# adc12-st.net
KiCad netlist of a schematic drawn in EAGLE
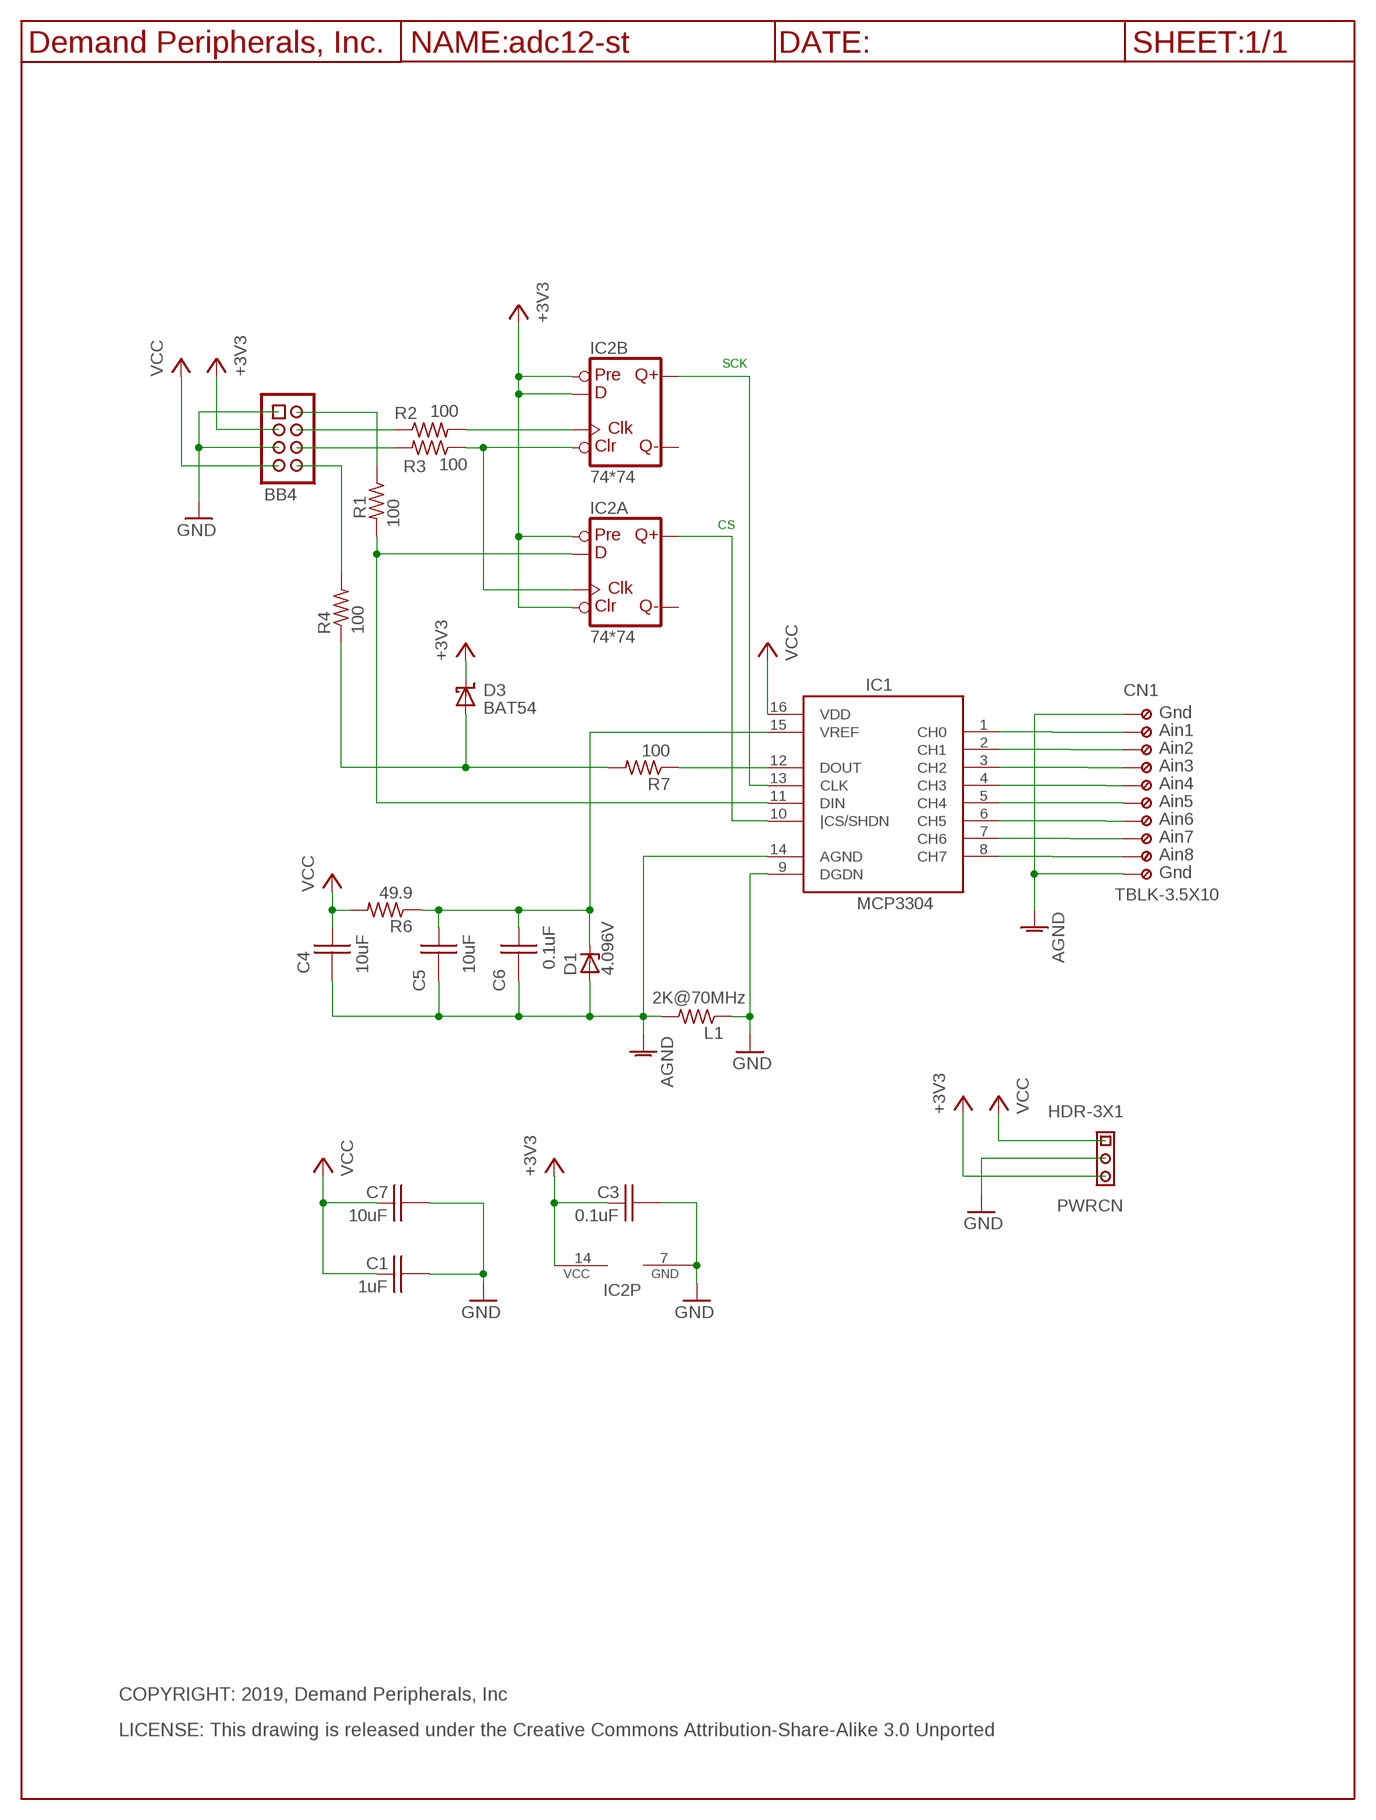
[diagram p0: schematic, sheet 1]

(export (version "E")
  (design (tool "Eeschema 10.0.6"))
  (components
    (comp (ref "BB4")
      (value "BB4_CON")
      (footprint "eagle-import:HDR-4X2")
      (libsource (lib "eagle-import") (part "HDR-4X2-SHR"))
    )
    (comp (ref "C1")
      (value "1uF")
      (footprint "eagle-import:C0603")
      (libsource (lib "eagle-import") (part "C1.0UF_C0603"))
    )
    (comp (ref "C3")
      (value "0.1uF")
      (footprint "eagle-import:C0603")
      (libsource (lib "eagle-import") (part "C0.1UF_C0603"))
    )
    (comp (ref "C4")
      (value "10uF")
      (footprint "eagle-import:C0805")
      (libsource (lib "eagle-import") (part "C10UF35V_C0805"))
    )
    (comp (ref "C5")
      (value "10uF")
      (footprint "eagle-import:C0805")
      (libsource (lib "eagle-import") (part "C10UF35V_C0805"))
    )
    (comp (ref "C6")
      (value "0.1uF")
      (footprint "eagle-import:C0603")
      (libsource (lib "eagle-import") (part "C0.1UF_C0603"))
    )
    (comp (ref "C7")
      (value "10uF")
      (footprint "eagle-import:C0805")
      (libsource (lib "eagle-import") (part "C10UF35V_C0805"))
    )
    (comp (ref "CN1")
      (value "TBLK-3.5X10")
      (footprint "eagle-import:TBLK-3.5X10")
      (libsource (lib "eagle-import") (part "TBLK-3.5X10"))
    )
    (comp (ref "D1")
      (value "4.096V")
      (footprint "eagle-import:SOT23")
      (libsource (lib "eagle-import") (part "LM4040"))
    )
    (comp (ref "D3")
      (value "BAT54")
      (footprint "eagle-import:SOT23")
      (libsource (lib "eagle-import") (part "BAT54"))
    )
    (comp (ref "IC1")
      (value "MCP3304")
      (footprint "eagle-import:SO16")
      (libsource (lib "eagle-import") (part "MCP3304"))
    )
    (comp (ref "IC2")
      (value "74*74")
      (footprint "eagle-import:SO14")
      (libsource (lib "eagle-import") (part "74AHC74SS"))
    )
    (comp (ref "L1")
      (value "2K@70MHz")
      (footprint "eagle-import:R0805")
      (libsource (lib "eagle-import") (part "L2K70MHZR0805"))
    )
    (comp (ref "PWRCN")
      (value "HDR-3X1")
      (footprint "eagle-import:HDR-3X1")
      (libsource (lib "eagle-import") (part "HDR-3X1"))
    )
    (comp (ref "R1")
      (value "100")
      (footprint "eagle-import:R0603")
      (libsource (lib "eagle-import") (part "R100_R0603"))
    )
    (comp (ref "R2")
      (value "100")
      (footprint "eagle-import:R0603")
      (libsource (lib "eagle-import") (part "R100_R0603"))
    )
    (comp (ref "R3")
      (value "100")
      (footprint "eagle-import:R0603")
      (libsource (lib "eagle-import") (part "R100_R0603"))
    )
    (comp (ref "R4")
      (value "100")
      (footprint "eagle-import:R0603")
      (libsource (lib "eagle-import") (part "R100_R0603"))
    )
    (comp (ref "R6")
      (value "49.9")
      (footprint "eagle-import:R0603")
      (libsource (lib "eagle-import") (part "R49.9R0603"))
    )
    (comp (ref "R7")
      (value "100")
      (footprint "eagle-import:R0603")
      (libsource (lib "eagle-import") (part "R100_R0603"))
    )
    (comp (ref "U$3")
      (value "DP_FRAME_P")
      (footprint "eagle-import:LETTER_P")
      (libsource (lib "eagle-import") (part "DP_FRAME_P"))
    )
  )
  (nets
    (net (code "1") (name "+3V3") (class "Default")
      (node (ref "BB4") (pin "3") (pinfunction "3_3") (pintype "passive"))
      (node (ref "C3") (pin "1") (pinfunction "1_1") (pintype "passive"))
      (node (ref "D3") (pin "3") (pinfunction "CC_3") (pintype "passive"))
      (node (ref "IC2") (pin "1") (pinfunction "CLR_1") (pintype "input"))
      (node (ref "IC2") (pin "10") (pinfunction "PRE_10") (pintype "input"))
      (node (ref "IC2") (pin "12") (pinfunction "D_12") (pintype "input"))
      (node (ref "IC2") (pin "14") (pinfunction "VCC_14") (pintype "power_in"))
      (node (ref "IC2") (pin "4") (pinfunction "PRE_4") (pintype "input"))
      (node (ref "PWRCN") (pin "3") (pinfunction "3_3") (pintype "passive"))
    )
    (net (code "2") (name "AGND") (class "Default")
      (node (ref "C4") (pin "2") (pinfunction "2_2") (pintype "passive"))
      (node (ref "C5") (pin "2") (pinfunction "2_2") (pintype "passive"))
      (node (ref "C6") (pin "2") (pinfunction "2_2") (pintype "passive"))
      (node (ref "CN1") (pin "1") (pinfunction "KL_1") (pintype "passive"))
      (node (ref "CN1") (pin "10") (pinfunction "KL9_10") (pintype "passive"))
      (node (ref "D1") (pin "2") (pinfunction "A_2") (pintype "passive"))
      (node (ref "IC1") (pin "14") (pinfunction "AGND_14") (pintype "bidirectional"))
      (node (ref "L1") (pin "2") (pinfunction "2_2") (pintype "passive"))
    )
    (net (code "3") (name "GND") (class "Default")
      (node (ref "BB4") (pin "1") (pinfunction "1_1") (pintype "passive"))
      (node (ref "BB4") (pin "5") (pinfunction "5_5") (pintype "passive"))
      (node (ref "C1") (pin "2") (pinfunction "2_2") (pintype "passive"))
      (node (ref "C3") (pin "2") (pinfunction "2_2") (pintype "passive"))
      (node (ref "C7") (pin "2") (pinfunction "2_2") (pintype "passive"))
      (node (ref "IC1") (pin "9") (pinfunction "DGDN_9") (pintype "bidirectional"))
      (node (ref "IC2") (pin "7") (pinfunction "GND_7") (pintype "power_in"))
      (node (ref "L1") (pin "1") (pinfunction "1_1") (pintype "passive"))
      (node (ref "PWRCN") (pin "2") (pinfunction "2_2") (pintype "passive"))
    )
    (net (code "4") (name "Net-(BB4-Pad2)") (class "Default")
      (node (ref "BB4") (pin "2") (pinfunction "2_2") (pintype "passive"))
      (node (ref "R1") (pin "1") (pinfunction "1_1") (pintype "passive"))
    )
    (net (code "5") (name "Net-(BB4-Pad4)") (class "Default")
      (node (ref "BB4") (pin "4") (pinfunction "4_4") (pintype "passive"))
      (node (ref "R2") (pin "1") (pinfunction "1_1") (pintype "passive"))
    )
    (net (code "6") (name "Net-(BB4-Pad6)") (class "Default")
      (node (ref "BB4") (pin "6") (pinfunction "6_6") (pintype "passive"))
      (node (ref "R3") (pin "2") (pinfunction "2_2") (pintype "passive"))
    )
    (net (code "7") (name "Net-(BB4-Pad8)") (class "Default")
      (node (ref "BB4") (pin "8") (pinfunction "8_8") (pintype "passive"))
      (node (ref "R4") (pin "2") (pinfunction "2_2") (pintype "passive"))
    )
    (net (code "8") (name "Net-(CN1-KL1)") (class "Default")
      (node (ref "CN1") (pin "2") (pinfunction "KL1_2") (pintype "passive"))
      (node (ref "IC1") (pin "1") (pinfunction "CH0_1") (pintype "bidirectional"))
    )
    (net (code "9") (name "Net-(CN1-KL2)") (class "Default")
      (node (ref "CN1") (pin "3") (pinfunction "KL2_3") (pintype "passive"))
      (node (ref "IC1") (pin "2") (pinfunction "CH1_2") (pintype "bidirectional"))
    )
    (net (code "10") (name "Net-(CN1-KL3)") (class "Default")
      (node (ref "CN1") (pin "4") (pinfunction "KL3_4") (pintype "passive"))
      (node (ref "IC1") (pin "3") (pinfunction "CH2_3") (pintype "bidirectional"))
    )
    (net (code "11") (name "Net-(CN1-KL4)") (class "Default")
      (node (ref "CN1") (pin "5") (pinfunction "KL4_5") (pintype "passive"))
      (node (ref "IC1") (pin "4") (pinfunction "CH3_4") (pintype "bidirectional"))
    )
    (net (code "12") (name "Net-(CN1-KL5)") (class "Default")
      (node (ref "CN1") (pin "6") (pinfunction "KL5_6") (pintype "passive"))
      (node (ref "IC1") (pin "5") (pinfunction "CH4_5") (pintype "bidirectional"))
    )
    (net (code "13") (name "Net-(CN1-KL6)") (class "Default")
      (node (ref "CN1") (pin "7") (pinfunction "KL6_7") (pintype "passive"))
      (node (ref "IC1") (pin "6") (pinfunction "CH5_6") (pintype "bidirectional"))
    )
    (net (code "14") (name "Net-(CN1-KL7)") (class "Default")
      (node (ref "CN1") (pin "8") (pinfunction "KL7_8") (pintype "passive"))
      (node (ref "IC1") (pin "7") (pinfunction "CH6_7") (pintype "bidirectional"))
    )
    (net (code "15") (name "Net-(CN1-KL8)") (class "Default")
      (node (ref "CN1") (pin "9") (pinfunction "KL8_9") (pintype "passive"))
      (node (ref "IC1") (pin "8") (pinfunction "CH7_8") (pintype "bidirectional"))
    )
    (net (code "16") (name "Net-(D1-C)") (class "Default")
      (node (ref "C5") (pin "1") (pinfunction "1_1") (pintype "passive"))
      (node (ref "C6") (pin "1") (pinfunction "1_1") (pintype "passive"))
      (node (ref "D1") (pin "1") (pinfunction "C_1") (pintype "passive"))
      (node (ref "IC1") (pin "15") (pinfunction "VREF_15") (pintype "bidirectional"))
      (node (ref "R6") (pin "1") (pinfunction "1_1") (pintype "passive"))
    )
    (net (code "17") (name "Net-(D3-A)") (class "Default")
      (node (ref "D3") (pin "1") (pinfunction "A_1") (pintype "passive"))
      (node (ref "R4") (pin "1") (pinfunction "1_1") (pintype "passive"))
      (node (ref "R7") (pin "2") (pinfunction "2_2") (pintype "passive"))
    )
    (net (code "18") (name "Net-(IC1-CLK)") (class "Default")
      (node (ref "IC1") (pin "13") (pinfunction "CLK_13") (pintype "bidirectional"))
      (node (ref "IC2") (pin "9") (pinfunction "Q_9") (pintype "output"))
    )
    (net (code "19") (name "Net-(IC1-DIN)") (class "Default")
      (node (ref "IC1") (pin "11") (pinfunction "DIN_11") (pintype "bidirectional"))
      (node (ref "IC2") (pin "2") (pinfunction "D_2") (pintype "input"))
      (node (ref "R1") (pin "2") (pinfunction "2_2") (pintype "passive"))
    )
    (net (code "20") (name "Net-(IC1-DOUT)") (class "Default")
      (node (ref "IC1") (pin "12") (pinfunction "DOUT_12") (pintype "bidirectional"))
      (node (ref "R7") (pin "1") (pinfunction "1_1") (pintype "passive"))
    )
    (net (code "21") (name "Net-(IC1-|CS{slash}SHDN)") (class "Default")
      (node (ref "IC1") (pin "10") (pinfunction "|CS/SHDN_10") (pintype "bidirectional"))
      (node (ref "IC2") (pin "5") (pinfunction "Q_5") (pintype "output"))
    )
    (net (code "22") (name "Net-(IC2A-CLK)") (class "Default")
      (node (ref "IC2") (pin "13") (pinfunction "CLR_13") (pintype "input"))
      (node (ref "IC2") (pin "3") (pinfunction "CLK_3") (pintype "input"))
      (node (ref "R3") (pin "1") (pinfunction "1_1") (pintype "passive"))
    )
    (net (code "23") (name "Net-(IC2B-CLK)") (class "Default")
      (node (ref "IC2") (pin "11") (pinfunction "CLK_11") (pintype "input"))
      (node (ref "R2") (pin "2") (pinfunction "2_2") (pintype "passive"))
    )
    (net (code "24") (name "VCC") (class "Default")
      (node (ref "BB4") (pin "7") (pinfunction "7_7") (pintype "passive"))
      (node (ref "C1") (pin "1") (pinfunction "1_1") (pintype "passive"))
      (node (ref "C4") (pin "1") (pinfunction "1_1") (pintype "passive"))
      (node (ref "C7") (pin "1") (pinfunction "1_1") (pintype "passive"))
      (node (ref "IC1") (pin "16") (pinfunction "VDD_16") (pintype "bidirectional"))
      (node (ref "PWRCN") (pin "1") (pinfunction "1_1") (pintype "passive"))
      (node (ref "R6") (pin "2") (pinfunction "2_2") (pintype "passive"))
    )
    (net (code "25") (name "unconnected-(IC2A-~{Q}-Pad6)") (class "Default")
      (node (ref "IC2") (pin "6") (pinfunction "~{Q}_6") (pintype "output"))
    )
    (net (code "26") (name "unconnected-(IC2B-~{Q}-Pad8)") (class "Default")
      (node (ref "IC2") (pin "8") (pinfunction "~{Q}_8") (pintype "output"))
    )
  )
)
